# Commandes.net
KiCad netlist of a schematic drawn in EAGLE
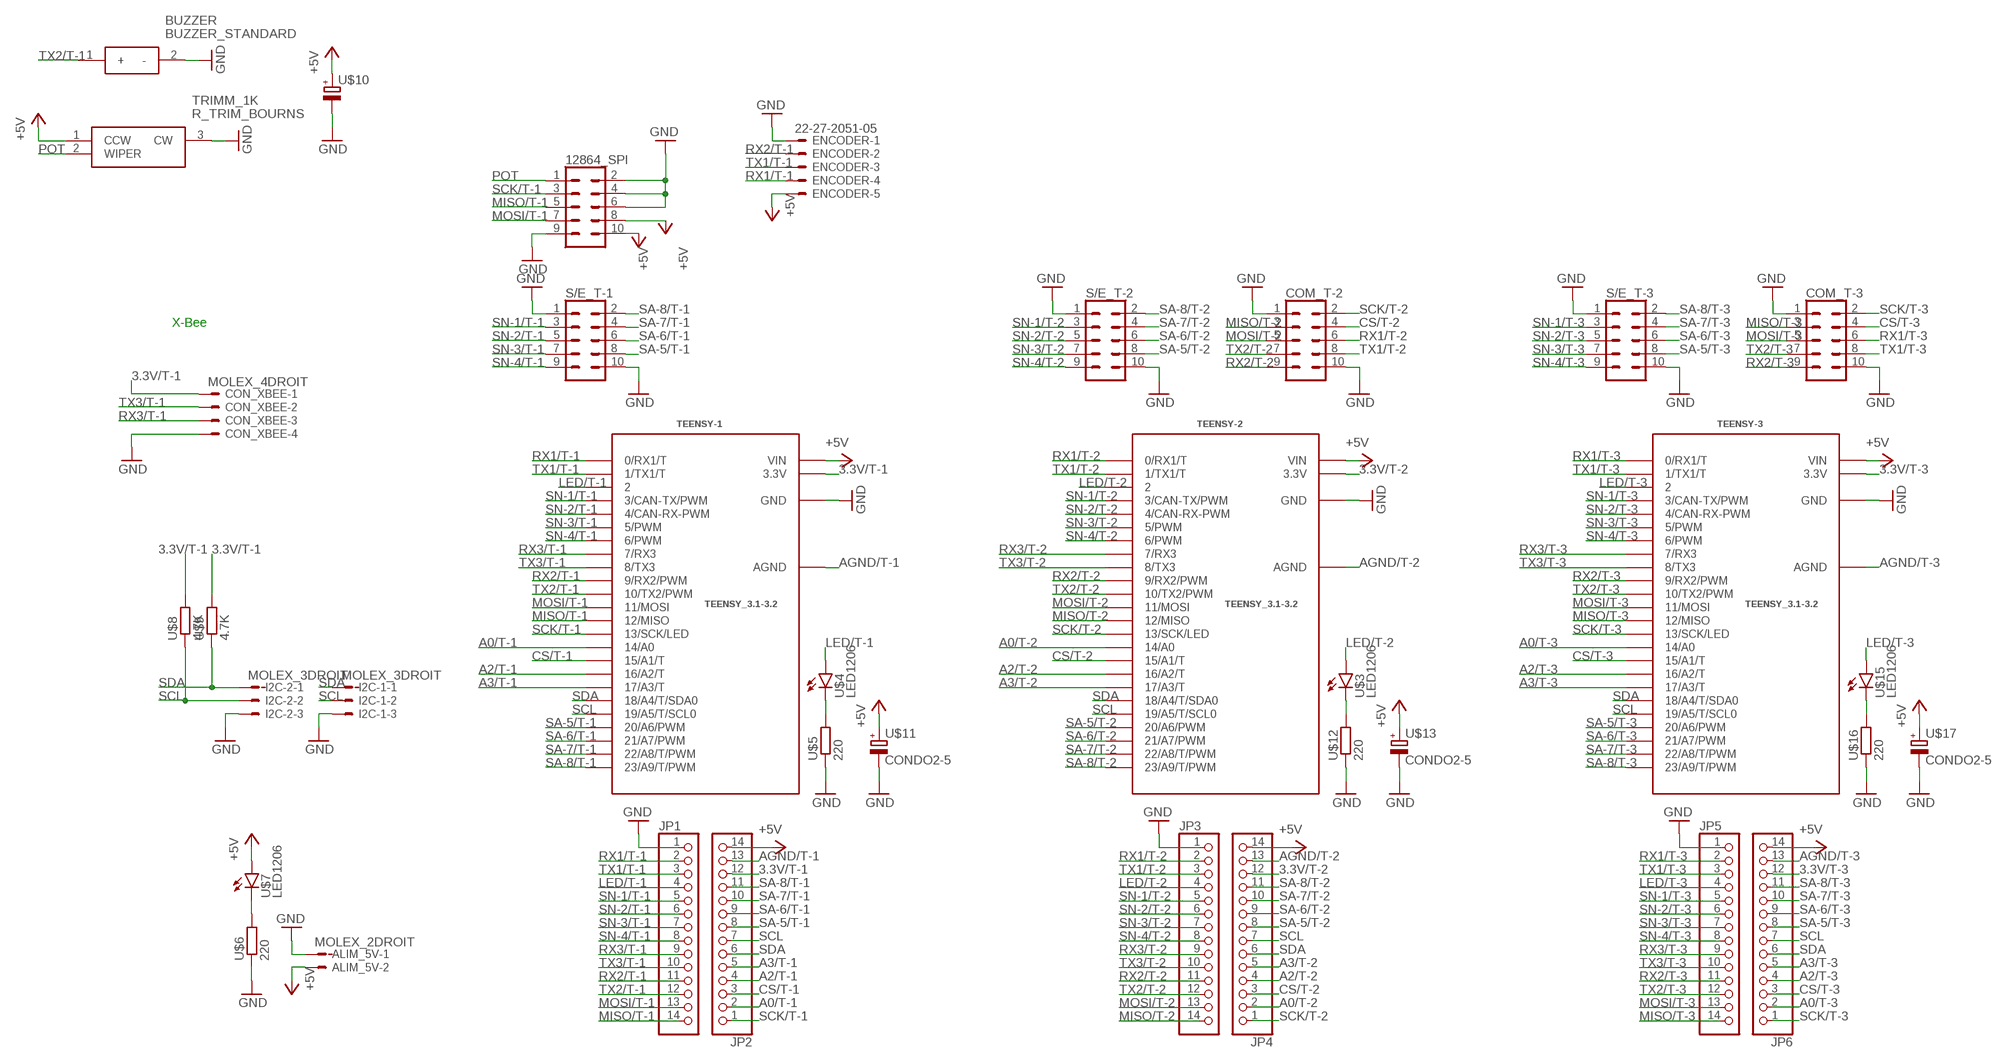
[diagram p0: schematic, sheet 1]

(export (version "E")
  (design (tool "Eeschema 10.0.6"))
  (components
    (comp (ref "12864_SPI")
      (value "CON_5X2SHD")
      (footprint "eagle-import:2X5-SHROUDED")
      (libsource (lib "eagle-import") (part "CON_5X2SHD"))
    )
    (comp (ref "ALIM_5V")
      (value "MOLEX_2DROIT")
      (footprint "eagle-import:CON_2_DROIT")
      (fields (field (name "MF") "MOLEX"))
      (libsource (lib "eagle-import") (part "MOLEX_2DROIT"))
    )
    (comp (ref "BUZZER")
      (value "BUZZER_STANDARD")
      (footprint "eagle-import:CEM-1203(42)")
      (fields (field (name "MANUFACTURER_PART_NUMBER") "CEM-1203(42)"))
      (libsource (lib "eagle-import") (part "BUZZER_STANDARD"))
    )
    (comp (ref "COM_T-2")
      (value "CON_5X2SHD")
      (footprint "eagle-import:2X5-SHROUDED")
      (libsource (lib "eagle-import") (part "CON_5X2SHD"))
    )
    (comp (ref "COM_T-3")
      (value "CON_5X2SHD")
      (footprint "eagle-import:2X5-SHROUDED")
      (libsource (lib "eagle-import") (part "CON_5X2SHD"))
    )
    (comp (ref "CON_XBEE")
      (value "MOLEX_4DROIT")
      (footprint "eagle-import:CON_4_DROIT")
      (fields (field (name "MF") "MOLEX"))
      (libsource (lib "eagle-import") (part "MOLEX_4DROIT"))
    )
    (comp (ref "ENCODER")
      (value "22-27-2051-05")
      (footprint "eagle-import:6410-05")
      (fields (field (name "MF") "MOLEX"))
      (libsource (lib "eagle-import") (part "22-?-0527-2051"))
    )
    (comp (ref "I2C-1")
      (value "MOLEX_3DROIT")
      (footprint "eagle-import:CON_3_DROIT")
      (fields (field (name "MF") "MOLEX"))
      (libsource (lib "eagle-import") (part "MOLEX_3DROIT"))
    )
    (comp (ref "I2C-2")
      (value "MOLEX_3DROIT")
      (footprint "eagle-import:CON_3_DROIT")
      (fields (field (name "MF") "MOLEX"))
      (libsource (lib "eagle-import") (part "MOLEX_3DROIT"))
    )
    (comp (ref "JP1")
      (value "PINHD-1X14_2.54")
      (footprint "eagle-import:1X14")
      (libsource (lib "eagle-import") (part "PINHD-1X14_2.54"))
    )
    (comp (ref "JP2")
      (value "PINHD-1X14_2.54")
      (footprint "eagle-import:1X14")
      (libsource (lib "eagle-import") (part "PINHD-1X14_2.54"))
    )
    (comp (ref "JP3")
      (value "PINHD-1X14_2.54")
      (footprint "eagle-import:1X14")
      (libsource (lib "eagle-import") (part "PINHD-1X14_2.54"))
    )
    (comp (ref "JP4")
      (value "PINHD-1X14_2.54")
      (footprint "eagle-import:1X14")
      (libsource (lib "eagle-import") (part "PINHD-1X14_2.54"))
    )
    (comp (ref "JP5")
      (value "PINHD-1X14_2.54")
      (footprint "eagle-import:1X14")
      (libsource (lib "eagle-import") (part "PINHD-1X14_2.54"))
    )
    (comp (ref "JP6")
      (value "PINHD-1X14_2.54")
      (footprint "eagle-import:1X14")
      (libsource (lib "eagle-import") (part "PINHD-1X14_2.54"))
    )
    (comp (ref "S/E_T-1")
      (value "CON_5X2SHD")
      (footprint "eagle-import:2X5-SHROUDED")
      (libsource (lib "eagle-import") (part "CON_5X2SHD"))
    )
    (comp (ref "S/E_T-2")
      (value "CON_5X2SHD")
      (footprint "eagle-import:2X5-SHROUDED")
      (libsource (lib "eagle-import") (part "CON_5X2SHD"))
    )
    (comp (ref "S/E_T-3")
      (value "CON_5X2SHD")
      (footprint "eagle-import:2X5-SHROUDED")
      (libsource (lib "eagle-import") (part "CON_5X2SHD"))
    )
    (comp (ref "TEENSY-1")
      (value "TEENSY_3.1-3.2")
      (footprint "eagle-import:TEENSY_3.0-3.2&LC_OUTER_ROW")
      (libsource (lib "eagle-import") (part "TEENSY_3.1-3.2"))
    )
    (comp (ref "TEENSY-2")
      (value "TEENSY_3.1-3.2")
      (footprint "eagle-import:TEENSY_3.0-3.2&LC_OUTER_ROW")
      (libsource (lib "eagle-import") (part "TEENSY_3.1-3.2"))
    )
    (comp (ref "TEENSY-3")
      (value "TEENSY_3.1-3.2")
      (footprint "eagle-import:TEENSY_3.0-3.2&LC_OUTER_ROW")
      (libsource (lib "eagle-import") (part "TEENSY_3.1-3.2"))
    )
    (comp (ref "TRIMM_1K")
      (value "R_TRIM_BOURNS")
      (footprint "eagle-import:3362P_1")
      (fields
        (field (name "MANUFACTURER_PART_NUMBER") "3362P-1-102LF")
        (field (name "MOUSER_PART_NUMBER") "652-3362P-1-102LF")
        (field (name "RS_PART_NUMBER") "1673252")
      )
      (libsource (lib "eagle-import") (part "R_TRIM_BOURNS"))
    )
    (comp (ref "U$3")
      (value "LED1206")
      (footprint "eagle-import:1206")
      (libsource (lib "eagle-import") (part "LED1206"))
    )
    (comp (ref "U$4")
      (value "LED1206")
      (footprint "eagle-import:1206")
      (libsource (lib "eagle-import") (part "LED1206"))
    )
    (comp (ref "U$5")
      (value "220")
      (footprint "eagle-import:R1206")
      (libsource (lib "eagle-import") (part "R1206R1206"))
    )
    (comp (ref "U$6")
      (value "220")
      (footprint "eagle-import:R1206")
      (libsource (lib "eagle-import") (part "R1206R1206"))
    )
    (comp (ref "U$7")
      (value "LED1206")
      (footprint "eagle-import:1206")
      (libsource (lib "eagle-import") (part "LED1206"))
    )
    (comp (ref "U$8")
      (value "4.7K")
      (footprint "eagle-import:R1206")
      (libsource (lib "eagle-import") (part "R1206R1206"))
    )
    (comp (ref "U$9")
      (value "4.7K")
      (footprint "eagle-import:R1206")
      (libsource (lib "eagle-import") (part "R1206R1206"))
    )
    (comp (ref "U$10")
      (value "CONDO2-5")
      (footprint "eagle-import:E2-5")
      (libsource (lib "eagle-import") (part "CONDO2-5"))
    )
    (comp (ref "U$11")
      (value "CONDO2-5")
      (footprint "eagle-import:E2-5")
      (libsource (lib "eagle-import") (part "CONDO2-5"))
    )
    (comp (ref "U$12")
      (value "220")
      (footprint "eagle-import:R1206")
      (libsource (lib "eagle-import") (part "R1206R1206"))
    )
    (comp (ref "U$13")
      (value "CONDO2-5")
      (footprint "eagle-import:E2-5")
      (libsource (lib "eagle-import") (part "CONDO2-5"))
    )
    (comp (ref "U$15")
      (value "LED1206")
      (footprint "eagle-import:1206")
      (libsource (lib "eagle-import") (part "LED1206"))
    )
    (comp (ref "U$16")
      (value "220")
      (footprint "eagle-import:R1206")
      (libsource (lib "eagle-import") (part "R1206R1206"))
    )
    (comp (ref "U$17")
      (value "CONDO2-5")
      (footprint "eagle-import:E2-5")
      (libsource (lib "eagle-import") (part "CONDO2-5"))
    )
  )
  (nets
    (net (code "1") (name "+5V") (class "Default")
      (node (ref "12864_SPI") (pin "10") (pinfunction "10_10") (pintype "passive"))
      (node (ref "12864_SPI") (pin "8") (pinfunction "8_8") (pintype "passive"))
      (node (ref "ALIM_5V") (pin "2") (pinfunction "S_2") (pintype "passive"))
      (node (ref "ENCODER") (pin "5") (pinfunction "S_5") (pintype "passive"))
      (node (ref "JP2") (pin "14") (pinfunction "14_14") (pintype "passive"))
      (node (ref "JP4") (pin "14") (pinfunction "14_14") (pintype "passive"))
      (node (ref "JP6") (pin "14") (pinfunction "14_14") (pintype "passive"))
      (node (ref "TEENSY-1") (pin "V_IN") (pinfunction "VIN_V_IN") (pintype "power_in"))
      (node (ref "TEENSY-2") (pin "V_IN") (pinfunction "VIN_V_IN") (pintype "power_in"))
      (node (ref "TEENSY-3") (pin "V_IN") (pinfunction "VIN_V_IN") (pintype "power_in"))
      (node (ref "TRIMM_1K") (pin "1") (pinfunction "CCW_1") (pintype "bidirectional"))
      (node (ref "U$10") (pin "+") (pinfunction "+_+") (pintype "passive"))
      (node (ref "U$11") (pin "+") (pinfunction "+_+") (pintype "passive"))
      (node (ref "U$13") (pin "+") (pinfunction "+_+") (pintype "passive"))
      (node (ref "U$17") (pin "+") (pinfunction "+_+") (pintype "passive"))
      (node (ref "U$7") (pin "A") (pinfunction "A_A") (pintype "passive"))
    )
    (net (code "2") (name "/3.3V{slash}T-1") (class "Default")
      (node (ref "CON_XBEE") (pin "1") (pinfunction "S_1") (pintype "passive"))
      (node (ref "JP2") (pin "12") (pinfunction "12_12") (pintype "passive"))
      (node (ref "TEENSY-1") (pin "3.3V") (pinfunction "3.3V_3.3V") (pintype "power_in"))
      (node (ref "U$8") (pin "2") (pinfunction "2_2") (pintype "passive"))
      (node (ref "U$9") (pin "2") (pinfunction "2_2") (pintype "passive"))
    )
    (net (code "3") (name "/3.3V{slash}T-2") (class "Default")
      (node (ref "JP4") (pin "12") (pinfunction "12_12") (pintype "passive"))
      (node (ref "TEENSY-2") (pin "3.3V") (pinfunction "3.3V_3.3V") (pintype "power_in"))
    )
    (net (code "4") (name "/3.3V{slash}T-3") (class "Default")
      (node (ref "JP6") (pin "12") (pinfunction "12_12") (pintype "passive"))
      (node (ref "TEENSY-3") (pin "3.3V") (pinfunction "3.3V_3.3V") (pintype "power_in"))
    )
    (net (code "5") (name "/A0{slash}T-1") (class "Default")
      (node (ref "JP2") (pin "2") (pinfunction "2_2") (pintype "passive"))
      (node (ref "TEENSY-1") (pin "14/A0") (pinfunction "14/A0_14/A0") (pintype "bidirectional"))
    )
    (net (code "6") (name "/A0{slash}T-2") (class "Default")
      (node (ref "JP4") (pin "2") (pinfunction "2_2") (pintype "passive"))
      (node (ref "TEENSY-2") (pin "14/A0") (pinfunction "14/A0_14/A0") (pintype "bidirectional"))
    )
    (net (code "7") (name "/A0{slash}T-3") (class "Default")
      (node (ref "JP6") (pin "2") (pinfunction "2_2") (pintype "passive"))
      (node (ref "TEENSY-3") (pin "14/A0") (pinfunction "14/A0_14/A0") (pintype "bidirectional"))
    )
    (net (code "8") (name "/A2{slash}T-1") (class "Default")
      (node (ref "JP2") (pin "4") (pinfunction "4_4") (pintype "passive"))
      (node (ref "TEENSY-1") (pin "16/A2") (pinfunction "16/A2/T_16/A2") (pintype "bidirectional"))
    )
    (net (code "9") (name "/A2{slash}T-2") (class "Default")
      (node (ref "JP4") (pin "4") (pinfunction "4_4") (pintype "passive"))
      (node (ref "TEENSY-2") (pin "16/A2") (pinfunction "16/A2/T_16/A2") (pintype "bidirectional"))
    )
    (net (code "10") (name "/A2{slash}T-3") (class "Default")
      (node (ref "JP6") (pin "4") (pinfunction "4_4") (pintype "passive"))
      (node (ref "TEENSY-3") (pin "16/A2") (pinfunction "16/A2/T_16/A2") (pintype "bidirectional"))
    )
    (net (code "11") (name "/A3{slash}T-1") (class "Default")
      (node (ref "JP2") (pin "5") (pinfunction "5_5") (pintype "passive"))
      (node (ref "TEENSY-1") (pin "17/A3") (pinfunction "17/A3/T_17/A3") (pintype "bidirectional"))
    )
    (net (code "12") (name "/A3{slash}T-2") (class "Default")
      (node (ref "JP4") (pin "5") (pinfunction "5_5") (pintype "passive"))
      (node (ref "TEENSY-2") (pin "17/A3") (pinfunction "17/A3/T_17/A3") (pintype "bidirectional"))
    )
    (net (code "13") (name "/A3{slash}T-3") (class "Default")
      (node (ref "JP6") (pin "5") (pinfunction "5_5") (pintype "passive"))
      (node (ref "TEENSY-3") (pin "17/A3") (pinfunction "17/A3/T_17/A3") (pintype "bidirectional"))
    )
    (net (code "14") (name "/AGND{slash}T-1") (class "Default")
      (node (ref "JP2") (pin "13") (pinfunction "13_13") (pintype "passive"))
      (node (ref "TEENSY-1") (pin "AGND") (pinfunction "AGND_AGND") (pintype "power_in"))
    )
    (net (code "15") (name "/AGND{slash}T-2") (class "Default")
      (node (ref "JP4") (pin "13") (pinfunction "13_13") (pintype "passive"))
      (node (ref "TEENSY-2") (pin "AGND") (pinfunction "AGND_AGND") (pintype "power_in"))
    )
    (net (code "16") (name "/AGND{slash}T-3") (class "Default")
      (node (ref "JP6") (pin "13") (pinfunction "13_13") (pintype "passive"))
      (node (ref "TEENSY-3") (pin "AGND") (pinfunction "AGND_AGND") (pintype "power_in"))
    )
    (net (code "17") (name "/CS{slash}T-1") (class "Default")
      (node (ref "JP2") (pin "3") (pinfunction "3_3") (pintype "passive"))
      (node (ref "TEENSY-1") (pin "15/A1") (pinfunction "15/A1/T_15/A1") (pintype "bidirectional"))
    )
    (net (code "18") (name "/CS{slash}T-2") (class "Default")
      (node (ref "COM_T-2") (pin "4") (pinfunction "4_4") (pintype "passive"))
      (node (ref "JP4") (pin "3") (pinfunction "3_3") (pintype "passive"))
      (node (ref "TEENSY-2") (pin "15/A1") (pinfunction "15/A1/T_15/A1") (pintype "bidirectional"))
    )
    (net (code "19") (name "/CS{slash}T-3") (class "Default")
      (node (ref "COM_T-3") (pin "4") (pinfunction "4_4") (pintype "passive"))
      (node (ref "JP6") (pin "3") (pinfunction "3_3") (pintype "passive"))
      (node (ref "TEENSY-3") (pin "15/A1") (pinfunction "15/A1/T_15/A1") (pintype "bidirectional"))
    )
    (net (code "20") (name "/LED{slash}T-1") (class "Default")
      (node (ref "JP1") (pin "4") (pinfunction "4_4") (pintype "passive"))
      (node (ref "TEENSY-1") (pin "2") (pinfunction "2_2") (pintype "bidirectional"))
      (node (ref "U$4") (pin "A") (pinfunction "A_A") (pintype "passive"))
    )
    (net (code "21") (name "/LED{slash}T-2") (class "Default")
      (node (ref "JP3") (pin "4") (pinfunction "4_4") (pintype "passive"))
      (node (ref "TEENSY-2") (pin "2") (pinfunction "2_2") (pintype "bidirectional"))
      (node (ref "U$3") (pin "A") (pinfunction "A_A") (pintype "passive"))
    )
    (net (code "22") (name "/LED{slash}T-3") (class "Default")
      (node (ref "JP5") (pin "4") (pinfunction "4_4") (pintype "passive"))
      (node (ref "TEENSY-3") (pin "2") (pinfunction "2_2") (pintype "bidirectional"))
      (node (ref "U$15") (pin "A") (pinfunction "A_A") (pintype "passive"))
    )
    (net (code "23") (name "/MISO{slash}T-1") (class "Default")
      (node (ref "12864_SPI") (pin "5") (pinfunction "5_5") (pintype "passive"))
      (node (ref "JP1") (pin "14") (pinfunction "14_14") (pintype "passive"))
      (node (ref "TEENSY-1") (pin "12") (pinfunction "12/MISO_12") (pintype "bidirectional"))
    )
    (net (code "24") (name "/MISO{slash}T-2") (class "Default")
      (node (ref "COM_T-2") (pin "3") (pinfunction "3_3") (pintype "passive"))
      (node (ref "JP3") (pin "14") (pinfunction "14_14") (pintype "passive"))
      (node (ref "TEENSY-2") (pin "12") (pinfunction "12/MISO_12") (pintype "bidirectional"))
    )
    (net (code "25") (name "/MISO{slash}T-3") (class "Default")
      (node (ref "COM_T-3") (pin "3") (pinfunction "3_3") (pintype "passive"))
      (node (ref "JP5") (pin "14") (pinfunction "14_14") (pintype "passive"))
      (node (ref "TEENSY-3") (pin "12") (pinfunction "12/MISO_12") (pintype "bidirectional"))
    )
    (net (code "26") (name "/MOSI{slash}T-1") (class "Default")
      (node (ref "12864_SPI") (pin "7") (pinfunction "7_7") (pintype "passive"))
      (node (ref "JP1") (pin "13") (pinfunction "13_13") (pintype "passive"))
      (node (ref "TEENSY-1") (pin "11") (pinfunction "11/MOSI_11") (pintype "bidirectional"))
    )
    (net (code "27") (name "/MOSI{slash}T-2") (class "Default")
      (node (ref "COM_T-2") (pin "5") (pinfunction "5_5") (pintype "passive"))
      (node (ref "JP3") (pin "13") (pinfunction "13_13") (pintype "passive"))
      (node (ref "TEENSY-2") (pin "11") (pinfunction "11/MOSI_11") (pintype "bidirectional"))
    )
    (net (code "28") (name "/MOSI{slash}T-3") (class "Default")
      (node (ref "COM_T-3") (pin "5") (pinfunction "5_5") (pintype "passive"))
      (node (ref "JP5") (pin "13") (pinfunction "13_13") (pintype "passive"))
      (node (ref "TEENSY-3") (pin "11") (pinfunction "11/MOSI_11") (pintype "bidirectional"))
    )
    (net (code "29") (name "/POT") (class "Default")
      (node (ref "12864_SPI") (pin "1") (pinfunction "1_1") (pintype "passive"))
      (node (ref "TRIMM_1K") (pin "2") (pinfunction "WIPER_2") (pintype "bidirectional"))
    )
    (net (code "30") (name "/RX1{slash}T-1") (class "Default")
      (node (ref "ENCODER") (pin "4") (pinfunction "S_4") (pintype "passive"))
      (node (ref "JP1") (pin "2") (pinfunction "2_2") (pintype "passive"))
      (node (ref "TEENSY-1") (pin "0") (pinfunction "0/RX1/T_0") (pintype "bidirectional"))
    )
    (net (code "31") (name "/RX1{slash}T-2") (class "Default")
      (node (ref "COM_T-2") (pin "6") (pinfunction "6_6") (pintype "passive"))
      (node (ref "JP3") (pin "2") (pinfunction "2_2") (pintype "passive"))
      (node (ref "TEENSY-2") (pin "0") (pinfunction "0/RX1/T_0") (pintype "bidirectional"))
    )
    (net (code "32") (name "/RX1{slash}T-3") (class "Default")
      (node (ref "COM_T-3") (pin "6") (pinfunction "6_6") (pintype "passive"))
      (node (ref "JP5") (pin "2") (pinfunction "2_2") (pintype "passive"))
      (node (ref "TEENSY-3") (pin "0") (pinfunction "0/RX1/T_0") (pintype "bidirectional"))
    )
    (net (code "33") (name "/RX2{slash}T-1") (class "Default")
      (node (ref "ENCODER") (pin "2") (pinfunction "S_2") (pintype "passive"))
      (node (ref "JP1") (pin "11") (pinfunction "11_11") (pintype "passive"))
      (node (ref "TEENSY-1") (pin "9") (pinfunction "9/RX2/PWM_9") (pintype "bidirectional"))
    )
    (net (code "34") (name "/RX2{slash}T-2") (class "Default")
      (node (ref "COM_T-2") (pin "9") (pinfunction "9_9") (pintype "passive"))
      (node (ref "JP3") (pin "11") (pinfunction "11_11") (pintype "passive"))
      (node (ref "TEENSY-2") (pin "9") (pinfunction "9/RX2/PWM_9") (pintype "bidirectional"))
    )
    (net (code "35") (name "/RX2{slash}T-3") (class "Default")
      (node (ref "COM_T-3") (pin "9") (pinfunction "9_9") (pintype "passive"))
      (node (ref "JP5") (pin "11") (pinfunction "11_11") (pintype "passive"))
      (node (ref "TEENSY-3") (pin "9") (pinfunction "9/RX2/PWM_9") (pintype "bidirectional"))
    )
    (net (code "36") (name "/RX3{slash}T-1") (class "Default")
      (node (ref "CON_XBEE") (pin "3") (pinfunction "S_3") (pintype "passive"))
      (node (ref "JP1") (pin "9") (pinfunction "9_9") (pintype "passive"))
      (node (ref "TEENSY-1") (pin "7") (pinfunction "7/RX3_7") (pintype "bidirectional"))
    )
    (net (code "37") (name "/RX3{slash}T-2") (class "Default")
      (node (ref "JP3") (pin "9") (pinfunction "9_9") (pintype "passive"))
      (node (ref "TEENSY-2") (pin "7") (pinfunction "7/RX3_7") (pintype "bidirectional"))
    )
    (net (code "38") (name "/RX3{slash}T-3") (class "Default")
      (node (ref "JP5") (pin "9") (pinfunction "9_9") (pintype "passive"))
      (node (ref "TEENSY-3") (pin "7") (pinfunction "7/RX3_7") (pintype "bidirectional"))
    )
    (net (code "39") (name "/SA-5{slash}T-1") (class "Default")
      (node (ref "JP2") (pin "8") (pinfunction "8_8") (pintype "passive"))
      (node (ref "S/E_T-1") (pin "8") (pinfunction "8_8") (pintype "passive"))
      (node (ref "TEENSY-1") (pin "20/A6") (pinfunction "20/A6/PWM_20/A6") (pintype "bidirectional"))
    )
    (net (code "40") (name "/SA-5{slash}T-2") (class "Default")
      (node (ref "JP4") (pin "8") (pinfunction "8_8") (pintype "passive"))
      (node (ref "S/E_T-2") (pin "8") (pinfunction "8_8") (pintype "passive"))
      (node (ref "TEENSY-2") (pin "20/A6") (pinfunction "20/A6/PWM_20/A6") (pintype "bidirectional"))
    )
    (net (code "41") (name "/SA-5{slash}T-3") (class "Default")
      (node (ref "JP6") (pin "8") (pinfunction "8_8") (pintype "passive"))
      (node (ref "S/E_T-3") (pin "8") (pinfunction "8_8") (pintype "passive"))
      (node (ref "TEENSY-3") (pin "20/A6") (pinfunction "20/A6/PWM_20/A6") (pintype "bidirectional"))
    )
    (net (code "42") (name "/SA-6{slash}T-1") (class "Default")
      (node (ref "JP2") (pin "9") (pinfunction "9_9") (pintype "passive"))
      (node (ref "S/E_T-1") (pin "6") (pinfunction "6_6") (pintype "passive"))
      (node (ref "TEENSY-1") (pin "21/A7") (pinfunction "21/A7/PWM_21/A7") (pintype "bidirectional"))
    )
    (net (code "43") (name "/SA-6{slash}T-2") (class "Default")
      (node (ref "JP4") (pin "9") (pinfunction "9_9") (pintype "passive"))
      (node (ref "S/E_T-2") (pin "6") (pinfunction "6_6") (pintype "passive"))
      (node (ref "TEENSY-2") (pin "21/A7") (pinfunction "21/A7/PWM_21/A7") (pintype "bidirectional"))
    )
    (net (code "44") (name "/SA-6{slash}T-3") (class "Default")
      (node (ref "JP6") (pin "9") (pinfunction "9_9") (pintype "passive"))
      (node (ref "S/E_T-3") (pin "6") (pinfunction "6_6") (pintype "passive"))
      (node (ref "TEENSY-3") (pin "21/A7") (pinfunction "21/A7/PWM_21/A7") (pintype "bidirectional"))
    )
    (net (code "45") (name "/SA-7{slash}T-1") (class "Default")
      (node (ref "JP2") (pin "10") (pinfunction "10_10") (pintype "passive"))
      (node (ref "S/E_T-1") (pin "4") (pinfunction "4_4") (pintype "passive"))
      (node (ref "TEENSY-1") (pin "22/A8") (pinfunction "22/A8/T/PWM_22/A8") (pintype "bidirectional"))
    )
    (net (code "46") (name "/SA-7{slash}T-2") (class "Default")
      (node (ref "JP4") (pin "10") (pinfunction "10_10") (pintype "passive"))
      (node (ref "S/E_T-2") (pin "4") (pinfunction "4_4") (pintype "passive"))
      (node (ref "TEENSY-2") (pin "22/A8") (pinfunction "22/A8/T/PWM_22/A8") (pintype "bidirectional"))
    )
    (net (code "47") (name "/SA-7{slash}T-3") (class "Default")
      (node (ref "JP6") (pin "10") (pinfunction "10_10") (pintype "passive"))
      (node (ref "S/E_T-3") (pin "4") (pinfunction "4_4") (pintype "passive"))
      (node (ref "TEENSY-3") (pin "22/A8") (pinfunction "22/A8/T/PWM_22/A8") (pintype "bidirectional"))
    )
    (net (code "48") (name "/SA-8{slash}T-1") (class "Default")
      (node (ref "JP2") (pin "11") (pinfunction "11_11") (pintype "passive"))
      (node (ref "S/E_T-1") (pin "2") (pinfunction "2_2") (pintype "passive"))
      (node (ref "TEENSY-1") (pin "23/A9") (pinfunction "23/A9/T/PWM_23/A9") (pintype "bidirectional"))
    )
    (net (code "49") (name "/SA-8{slash}T-2") (class "Default")
      (node (ref "JP4") (pin "11") (pinfunction "11_11") (pintype "passive"))
      (node (ref "S/E_T-2") (pin "2") (pinfunction "2_2") (pintype "passive"))
      (node (ref "TEENSY-2") (pin "23/A9") (pinfunction "23/A9/T/PWM_23/A9") (pintype "bidirectional"))
    )
    (net (code "50") (name "/SA-8{slash}T-3") (class "Default")
      (node (ref "JP6") (pin "11") (pinfunction "11_11") (pintype "passive"))
      (node (ref "S/E_T-3") (pin "2") (pinfunction "2_2") (pintype "passive"))
      (node (ref "TEENSY-3") (pin "23/A9") (pinfunction "23/A9/T/PWM_23/A9") (pintype "bidirectional"))
    )
    (net (code "51") (name "/SCK{slash}T-1") (class "Default")
      (node (ref "12864_SPI") (pin "3") (pinfunction "3_3") (pintype "passive"))
      (node (ref "JP2") (pin "1") (pinfunction "1_1") (pintype "passive"))
      (node (ref "TEENSY-1") (pin "13") (pinfunction "13/SCK/LED_13") (pintype "bidirectional"))
    )
    (net (code "52") (name "/SCK{slash}T-2") (class "Default")
      (node (ref "COM_T-2") (pin "2") (pinfunction "2_2") (pintype "passive"))
      (node (ref "JP4") (pin "1") (pinfunction "1_1") (pintype "passive"))
      (node (ref "TEENSY-2") (pin "13") (pinfunction "13/SCK/LED_13") (pintype "bidirectional"))
    )
    (net (code "53") (name "/SCK{slash}T-3") (class "Default")
      (node (ref "COM_T-3") (pin "2") (pinfunction "2_2") (pintype "passive"))
      (node (ref "JP6") (pin "1") (pinfunction "1_1") (pintype "passive"))
      (node (ref "TEENSY-3") (pin "13") (pinfunction "13/SCK/LED_13") (pintype "bidirectional"))
    )
    (net (code "54") (name "/SCL") (class "Default")
      (node (ref "I2C-1") (pin "2") (pinfunction "S_2") (pintype "passive"))
      (node (ref "I2C-2") (pin "2") (pinfunction "S_2") (pintype "passive"))
      (node (ref "JP2") (pin "7") (pinfunction "7_7") (pintype "passive"))
      (node (ref "JP4") (pin "7") (pinfunction "7_7") (pintype "passive"))
      (node (ref "JP6") (pin "7") (pinfunction "7_7") (pintype "passive"))
      (node (ref "TEENSY-1") (pin "19/A5") (pinfunction "19/A5/T/SCL0_19/A5") (pintype "bidirectional"))
      (node (ref "TEENSY-2") (pin "19/A5") (pinfunction "19/A5/T/SCL0_19/A5") (pintype "bidirectional"))
      (node (ref "TEENSY-3") (pin "19/A5") (pinfunction "19/A5/T/SCL0_19/A5") (pintype "bidirectional"))
      (node (ref "U$8") (pin "1") (pinfunction "1_1") (pintype "passive"))
    )
    (net (code "55") (name "/SDA") (class "Default")
      (node (ref "I2C-1") (pin "1") (pinfunction "S_1") (pintype "passive"))
      (node (ref "I2C-2") (pin "1") (pinfunction "S_1") (pintype "passive"))
      (node (ref "JP2") (pin "6") (pinfunction "6_6") (pintype "passive"))
      (node (ref "JP4") (pin "6") (pinfunction "6_6") (pintype "passive"))
      (node (ref "JP6") (pin "6") (pinfunction "6_6") (pintype "passive"))
      (node (ref "TEENSY-1") (pin "18/A4") (pinfunction "18/A4/T/SDA0_18/A4") (pintype "bidirectional"))
      (node (ref "TEENSY-2") (pin "18/A4") (pinfunction "18/A4/T/SDA0_18/A4") (pintype "bidirectional"))
      (node (ref "TEENSY-3") (pin "18/A4") (pinfunction "18/A4/T/SDA0_18/A4") (pintype "bidirectional"))
      (node (ref "U$9") (pin "1") (pinfunction "1_1") (pintype "passive"))
    )
    (net (code "56") (name "/SN-1{slash}T-1") (class "Default")
      (node (ref "JP1") (pin "5") (pinfunction "5_5") (pintype "passive"))
      (node (ref "S/E_T-1") (pin "3") (pinfunction "3_3") (pintype "passive"))
      (node (ref "TEENSY-1") (pin "3") (pinfunction "3/CAN-TX/PWM_3") (pintype "bidirectional"))
    )
    (net (code "57") (name "/SN-1{slash}T-2") (class "Default")
      (node (ref "JP3") (pin "5") (pinfunction "5_5") (pintype "passive"))
      (node (ref "S/E_T-2") (pin "3") (pinfunction "3_3") (pintype "passive"))
      (node (ref "TEENSY-2") (pin "3") (pinfunction "3/CAN-TX/PWM_3") (pintype "bidirectional"))
    )
    (net (code "58") (name "/SN-1{slash}T-3") (class "Default")
      (node (ref "JP5") (pin "5") (pinfunction "5_5") (pintype "passive"))
      (node (ref "S/E_T-3") (pin "3") (pinfunction "3_3") (pintype "passive"))
      (node (ref "TEENSY-3") (pin "3") (pinfunction "3/CAN-TX/PWM_3") (pintype "bidirectional"))
    )
    (net (code "59") (name "/SN-2{slash}T-1") (class "Default")
      (node (ref "JP1") (pin "6") (pinfunction "6_6") (pintype "passive"))
      (node (ref "S/E_T-1") (pin "5") (pinfunction "5_5") (pintype "passive"))
      (node (ref "TEENSY-1") (pin "4") (pinfunction "4/CAN-RX-PWM_4") (pintype "bidirectional"))
    )
    (net (code "60") (name "/SN-2{slash}T-2") (class "Default")
      (node (ref "JP3") (pin "6") (pinfunction "6_6") (pintype "passive"))
      (node (ref "S/E_T-2") (pin "5") (pinfunction "5_5") (pintype "passive"))
      (node (ref "TEENSY-2") (pin "4") (pinfunction "4/CAN-RX-PWM_4") (pintype "bidirectional"))
    )
    (net (code "61") (name "/SN-2{slash}T-3") (class "Default")
      (node (ref "JP5") (pin "6") (pinfunction "6_6") (pintype "passive"))
      (node (ref "S/E_T-3") (pin "5") (pinfunction "5_5") (pintype "passive"))
      (node (ref "TEENSY-3") (pin "4") (pinfunction "4/CAN-RX-PWM_4") (pintype "bidirectional"))
    )
    (net (code "62") (name "/SN-3{slash}T-1") (class "Default")
      (node (ref "JP1") (pin "7") (pinfunction "7_7") (pintype "passive"))
      (node (ref "S/E_T-1") (pin "7") (pinfunction "7_7") (pintype "passive"))
      (node (ref "TEENSY-1") (pin "5") (pinfunction "5/PWM_5") (pintype "bidirectional"))
    )
    (net (code "63") (name "/SN-3{slash}T-2") (class "Default")
      (node (ref "JP3") (pin "7") (pinfunction "7_7") (pintype "passive"))
      (node (ref "S/E_T-2") (pin "7") (pinfunction "7_7") (pintype "passive"))
      (node (ref "TEENSY-2") (pin "5") (pinfunction "5/PWM_5") (pintype "bidirectional"))
    )
    (net (code "64") (name "/SN-3{slash}T-3") (class "Default")
      (node (ref "JP5") (pin "7") (pinfunction "7_7") (pintype "passive"))
      (node (ref "S/E_T-3") (pin "7") (pinfunction "7_7") (pintype "passive"))
      (node (ref "TEENSY-3") (pin "5") (pinfunction "5/PWM_5") (pintype "bidirectional"))
    )
    (net (code "65") (name "/SN-4{slash}T-1") (class "Default")
      (node (ref "JP1") (pin "8") (pinfunction "8_8") (pintype "passive"))
      (node (ref "S/E_T-1") (pin "9") (pinfunction "9_9") (pintype "passive"))
      (node (ref "TEENSY-1") (pin "6") (pinfunction "6/PWM_6") (pintype "bidirectional"))
    )
    (net (code "66") (name "/SN-4{slash}T-2") (class "Default")
      (node (ref "JP3") (pin "8") (pinfunction "8_8") (pintype "passive"))
      (node (ref "S/E_T-2") (pin "9") (pinfunction "9_9") (pintype "passive"))
      (node (ref "TEENSY-2") (pin "6") (pinfunction "6/PWM_6") (pintype "bidirectional"))
    )
    (net (code "67") (name "/SN-4{slash}T-3") (class "Default")
      (node (ref "JP5") (pin "8") (pinfunction "8_8") (pintype "passive"))
      (node (ref "S/E_T-3") (pin "9") (pinfunction "9_9") (pintype "passive"))
      (node (ref "TEENSY-3") (pin "6") (pinfunction "6/PWM_6") (pintype "bidirectional"))
    )
    (net (code "68") (name "/TX1{slash}T-1") (class "Default")
      (node (ref "ENCODER") (pin "3") (pinfunction "S_3") (pintype "passive"))
      (node (ref "JP1") (pin "3") (pinfunction "3_3") (pintype "passive"))
      (node (ref "TEENSY-1") (pin "1") (pinfunction "1/TX1/T_1") (pintype "bidirectional"))
    )
    (net (code "69") (name "/TX1{slash}T-2") (class "Default")
      (node (ref "COM_T-2") (pin "8") (pinfunction "8_8") (pintype "passive"))
      (node (ref "JP3") (pin "3") (pinfunction "3_3") (pintype "passive"))
      (node (ref "TEENSY-2") (pin "1") (pinfunction "1/TX1/T_1") (pintype "bidirectional"))
    )
    (net (code "70") (name "/TX1{slash}T-3") (class "Default")
      (node (ref "COM_T-3") (pin "8") (pinfunction "8_8") (pintype "passive"))
      (node (ref "JP5") (pin "3") (pinfunction "3_3") (pintype "passive"))
      (node (ref "TEENSY-3") (pin "1") (pinfunction "1/TX1/T_1") (pintype "bidirectional"))
    )
    (net (code "71") (name "/TX2{slash}T-1") (class "Default")
      (node (ref "BUZZER") (pin "1") (pinfunction "+_1") (pintype "bidirectional"))
      (node (ref "JP1") (pin "12") (pinfunction "12_12") (pintype "passive"))
      (node (ref "TEENSY-1") (pin "10") (pinfunction "10/TX2/PWM_10") (pintype "bidirectional"))
    )
    (net (code "72") (name "/TX2{slash}T-2") (class "Default")
      (node (ref "COM_T-2") (pin "7") (pinfunction "7_7") (pintype "passive"))
      (node (ref "JP3") (pin "12") (pinfunction "12_12") (pintype "passive"))
      (node (ref "TEENSY-2") (pin "10") (pinfunction "10/TX2/PWM_10") (pintype "bidirectional"))
    )
    (net (code "73") (name "/TX2{slash}T-3") (class "Default")
      (node (ref "COM_T-3") (pin "7") (pinfunction "7_7") (pintype "passive"))
      (node (ref "JP5") (pin "12") (pinfunction "12_12") (pintype "passive"))
      (node (ref "TEENSY-3") (pin "10") (pinfunction "10/TX2/PWM_10") (pintype "bidirectional"))
    )
    (net (code "74") (name "/TX3{slash}T-1") (class "Default")
      (node (ref "CON_XBEE") (pin "2") (pinfunction "S_2") (pintype "passive"))
      (node (ref "JP1") (pin "10") (pinfunction "10_10") (pintype "passive"))
      (node (ref "TEENSY-1") (pin "8") (pinfunction "8/TX3_8") (pintype "bidirectional"))
    )
    (net (code "75") (name "/TX3{slash}T-2") (class "Default")
      (node (ref "JP3") (pin "10") (pinfunction "10_10") (pintype "passive"))
      (node (ref "TEENSY-2") (pin "8") (pinfunction "8/TX3_8") (pintype "bidirectional"))
    )
    (net (code "76") (name "/TX3{slash}T-3") (class "Default")
      (node (ref "JP5") (pin "10") (pinfunction "10_10") (pintype "passive"))
      (node (ref "TEENSY-3") (pin "8") (pinfunction "8/TX3_8") (pintype "bidirectional"))
    )
    (net (code "77") (name "GND") (class "Default")
      (node (ref "12864_SPI") (pin "2") (pinfunction "2_2") (pintype "passive"))
      (node (ref "12864_SPI") (pin "4") (pinfunction "4_4") (pintype "passive"))
      (node (ref "12864_SPI") (pin "6") (pinfunction "6_6") (pintype "passive"))
      (node (ref "12864_SPI") (pin "9") (pinfunction "9_9") (pintype "passive"))
      (node (ref "ALIM_5V") (pin "1") (pinfunction "S_1") (pintype "passive"))
      (node (ref "BUZZER") (pin "2") (pinfunction "-_2") (pintype "bidirectional"))
      (node (ref "COM_T-2") (pin "1") (pinfunction "1_1") (pintype "passive"))
      (node (ref "COM_T-2") (pin "10") (pinfunction "10_10") (pintype "passive"))
      (node (ref "COM_T-3") (pin "1") (pinfunction "1_1") (pintype "passive"))
      (node (ref "COM_T-3") (pin "10") (pinfunction "10_10") (pintype "passive"))
      (node (ref "CON_XBEE") (pin "4") (pinfunction "S_4") (pintype "passive"))
      (node (ref "ENCODER") (pin "1") (pinfunction "S_1") (pintype "passive"))
      (node (ref "I2C-1") (pin "3") (pinfunction "S_3") (pintype "passive"))
      (node (ref "I2C-2") (pin "3") (pinfunction "S_3") (pintype "passive"))
      (node (ref "JP1") (pin "1") (pinfunction "1_1") (pintype "passive"))
      (node (ref "JP3") (pin "1") (pinfunction "1_1") (pintype "passive"))
      (node (ref "JP5") (pin "1") (pinfunction "1_1") (pintype "passive"))
      (node (ref "S/E_T-1") (pin "1") (pinfunction "1_1") (pintype "passive"))
      (node (ref "S/E_T-1") (pin "10") (pinfunction "10_10") (pintype "passive"))
      (node (ref "S/E_T-2") (pin "1") (pinfunction "1_1") (pintype "passive"))
      (node (ref "S/E_T-2") (pin "10") (pinfunction "10_10") (pintype "passive"))
      (node (ref "S/E_T-3") (pin "1") (pinfunction "1_1") (pintype "passive"))
      (node (ref "S/E_T-3") (pin "10") (pinfunction "10_10") (pintype "passive"))
      (node (ref "TEENSY-1") (pin "GND") (pinfunction "GND_GND") (pintype "power_in"))
      (node (ref "TEENSY-2") (pin "GND") (pinfunction "GND_GND") (pintype "power_in"))
      (node (ref "TEENSY-3") (pin "GND") (pinfunction "GND_GND") (pintype "power_in"))
      (node (ref "TRIMM_1K") (pin "3") (pinfunction "CW_3") (pintype "bidirectional"))
      (node (ref "U$10") (pin "-") (pinfunction "-_-") (pintype "passive"))
      (node (ref "U$11") (pin "-") (pinfunction "-_-") (pintype "passive"))
      (node (ref "U$12") (pin "1") (pinfunction "1_1") (pintype "passive"))
      (node (ref "U$13") (pin "-") (pinfunction "-_-") (pintype "passive"))
      (node (ref "U$16") (pin "1") (pinfunction "1_1") (pintype "passive"))
      (node (ref "U$17") (pin "-") (pinfunction "-_-") (pintype "passive"))
      (node (ref "U$5") (pin "1") (pinfunction "1_1") (pintype "passive"))
      (node (ref "U$6") (pin "1") (pinfunction "1_1") (pintype "passive"))
    )
    (net (code "78") (name "Net-(U$4-PadC)") (class "Default")
      (node (ref "U$4") (pin "C") (pinfunction "C_C") (pintype "passive"))
      (node (ref "U$5") (pin "2") (pinfunction "2_2") (pintype "passive"))
    )
    (net (code "79") (name "Net-(U$6-Pad2)") (class "Default")
      (node (ref "U$6") (pin "2") (pinfunction "2_2") (pintype "passive"))
      (node (ref "U$7") (pin "C") (pinfunction "C_C") (pintype "passive"))
    )
    (net (code "80") (name "Net-(U$12-Pad2)") (class "Default")
      (node (ref "U$12") (pin "2") (pinfunction "2_2") (pintype "passive"))
      (node (ref "U$3") (pin "C") (pinfunction "C_C") (pintype "passive"))
    )
    (net (code "81") (name "Net-(U$15-PadC)") (class "Default")
      (node (ref "U$15") (pin "C") (pinfunction "C_C") (pintype "passive"))
      (node (ref "U$16") (pin "2") (pinfunction "2_2") (pintype "passive"))
    )
  )
)
